# base.net
KiCad netlist of a schematic drawn in EAGLE
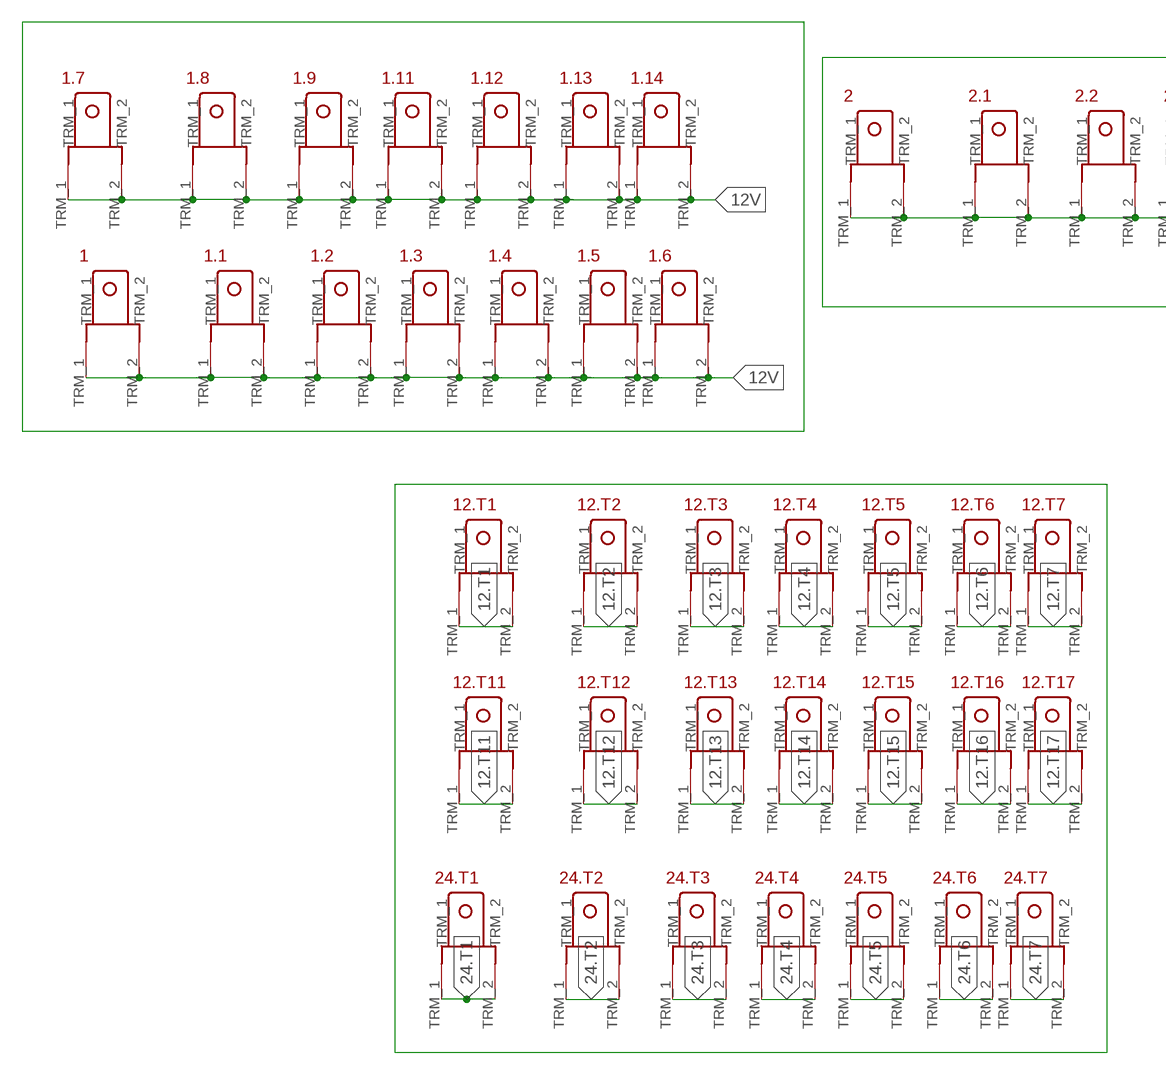
[diagram p0: schematic, sheet 1, part 1 of 2]
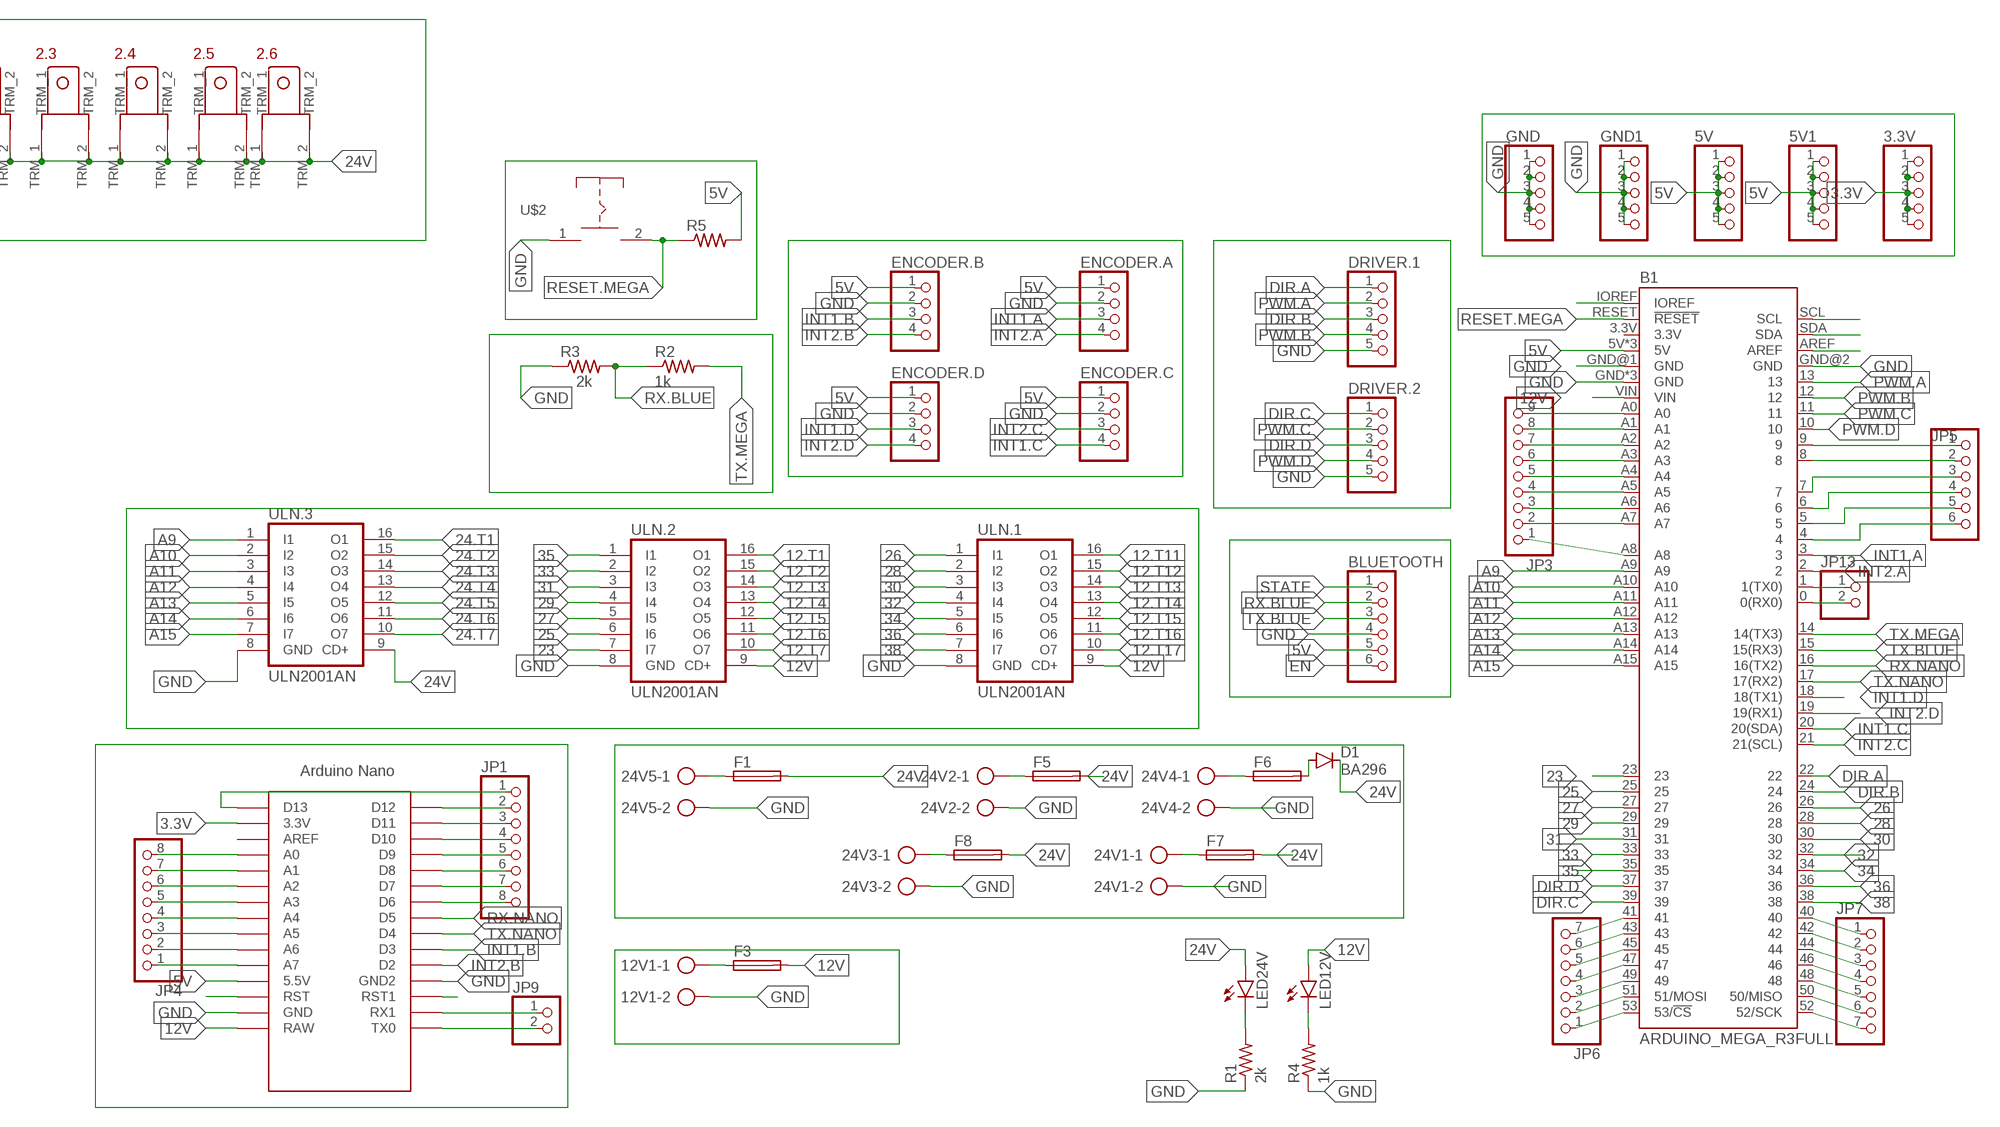
[diagram p1: schematic, sheet 1, part 2 of 2]

(export (version "E")
  (design (tool "Eeschema 10.0.6"))
  (components
    (comp (ref "1")
      (value "TERMINAL_EDITED")
      (footprint "eagle-import:TERMINAL_EDITED")
      (libsource (lib "eagle-import") (part "TERMINAL_EDITED"))
    )
    (comp (ref "1.1")
      (value "TERMINAL_EDITED")
      (footprint "eagle-import:TERMINAL_EDITED")
      (libsource (lib "eagle-import") (part "TERMINAL_EDITED"))
    )
    (comp (ref "1.2")
      (value "TERMINAL_EDITED")
      (footprint "eagle-import:TERMINAL_EDITED")
      (libsource (lib "eagle-import") (part "TERMINAL_EDITED"))
    )
    (comp (ref "1.3")
      (value "TERMINAL_EDITED")
      (footprint "eagle-import:TERMINAL_EDITED")
      (libsource (lib "eagle-import") (part "TERMINAL_EDITED"))
    )
    (comp (ref "1.4")
      (value "TERMINAL_EDITED")
      (footprint "eagle-import:TERMINAL_EDITED")
      (libsource (lib "eagle-import") (part "TERMINAL_EDITED"))
    )
    (comp (ref "1.5")
      (value "TERMINAL_EDITED")
      (footprint "eagle-import:TERMINAL_EDITED")
      (libsource (lib "eagle-import") (part "TERMINAL_EDITED"))
    )
    (comp (ref "1.6")
      (value "TERMINAL_EDITED")
      (footprint "eagle-import:TERMINAL_EDITED")
      (libsource (lib "eagle-import") (part "TERMINAL_EDITED"))
    )
    (comp (ref "1.7")
      (value "TERMINAL_EDITED")
      (footprint "eagle-import:TERMINAL_EDITED")
      (libsource (lib "eagle-import") (part "TERMINAL_EDITED"))
    )
    (comp (ref "1.8")
      (value "TERMINAL_EDITED")
      (footprint "eagle-import:TERMINAL_EDITED")
      (libsource (lib "eagle-import") (part "TERMINAL_EDITED"))
    )
    (comp (ref "1.9")
      (value "TERMINAL_EDITED")
      (footprint "eagle-import:TERMINAL_EDITED")
      (libsource (lib "eagle-import") (part "TERMINAL_EDITED"))
    )
    (comp (ref "1.11")
      (value "TERMINAL_EDITED")
      (footprint "eagle-import:TERMINAL_EDITED")
      (libsource (lib "eagle-import") (part "TERMINAL_EDITED"))
    )
    (comp (ref "1.12")
      (value "TERMINAL_EDITED")
      (footprint "eagle-import:TERMINAL_EDITED")
      (libsource (lib "eagle-import") (part "TERMINAL_EDITED"))
    )
    (comp (ref "1.13")
      (value "TERMINAL_EDITED")
      (footprint "eagle-import:TERMINAL_EDITED")
      (libsource (lib "eagle-import") (part "TERMINAL_EDITED"))
    )
    (comp (ref "1.14")
      (value "TERMINAL_EDITED")
      (footprint "eagle-import:TERMINAL_EDITED")
      (libsource (lib "eagle-import") (part "TERMINAL_EDITED"))
    )
    (comp (ref "2")
      (value "TERMINAL_EDITED")
      (footprint "eagle-import:TERMINAL_EDITED")
      (libsource (lib "eagle-import") (part "TERMINAL_EDITED"))
    )
    (comp (ref "2.1")
      (value "TERMINAL_EDITED")
      (footprint "eagle-import:TERMINAL_EDITED")
      (libsource (lib "eagle-import") (part "TERMINAL_EDITED"))
    )
    (comp (ref "2.2")
      (value "TERMINAL_EDITED")
      (footprint "eagle-import:TERMINAL_EDITED")
      (libsource (lib "eagle-import") (part "TERMINAL_EDITED"))
    )
    (comp (ref "2.3")
      (value "TERMINAL_EDITED")
      (footprint "eagle-import:TERMINAL_EDITED")
      (libsource (lib "eagle-import") (part "TERMINAL_EDITED"))
    )
    (comp (ref "2.4")
      (value "TERMINAL_EDITED")
      (footprint "eagle-import:TERMINAL_EDITED")
      (libsource (lib "eagle-import") (part "TERMINAL_EDITED"))
    )
    (comp (ref "2.5")
      (value "TERMINAL_EDITED")
      (footprint "eagle-import:TERMINAL_EDITED")
      (libsource (lib "eagle-import") (part "TERMINAL_EDITED"))
    )
    (comp (ref "2.6")
      (value "TERMINAL_EDITED")
      (footprint "eagle-import:TERMINAL_EDITED")
      (libsource (lib "eagle-import") (part "TERMINAL_EDITED"))
    )
    (comp (ref "3.3V")
      (value "PINHD-1X5")
      (footprint "eagle-import:1X05")
      (libsource (lib "eagle-import") (part "PINHD-1X5"))
    )
    (comp (ref "5V")
      (value "PINHD-1X5")
      (footprint "eagle-import:1X05")
      (libsource (lib "eagle-import") (part "PINHD-1X5"))
    )
    (comp (ref "5V1")
      (value "PINHD-1X5")
      (footprint "eagle-import:1X05")
      (libsource (lib "eagle-import") (part "PINHD-1X5"))
    )
    (comp (ref "12.T1")
      (value "TERMINAL_EDITED")
      (footprint "eagle-import:TERMINAL_EDITED")
      (libsource (lib "eagle-import") (part "TERMINAL_EDITED"))
    )
    (comp (ref "12.T2")
      (value "TERMINAL_EDITED")
      (footprint "eagle-import:TERMINAL_EDITED")
      (libsource (lib "eagle-import") (part "TERMINAL_EDITED"))
    )
    (comp (ref "12.T3")
      (value "TERMINAL_EDITED")
      (footprint "eagle-import:TERMINAL_EDITED")
      (libsource (lib "eagle-import") (part "TERMINAL_EDITED"))
    )
    (comp (ref "12.T4")
      (value "TERMINAL_EDITED")
      (footprint "eagle-import:TERMINAL_EDITED")
      (libsource (lib "eagle-import") (part "TERMINAL_EDITED"))
    )
    (comp (ref "12.T5")
      (value "TERMINAL_EDITED")
      (footprint "eagle-import:TERMINAL_EDITED")
      (libsource (lib "eagle-import") (part "TERMINAL_EDITED"))
    )
    (comp (ref "12.T6")
      (value "TERMINAL_EDITED")
      (footprint "eagle-import:TERMINAL_EDITED")
      (libsource (lib "eagle-import") (part "TERMINAL_EDITED"))
    )
    (comp (ref "12.T7")
      (value "TERMINAL_EDITED")
      (footprint "eagle-import:TERMINAL_EDITED")
      (libsource (lib "eagle-import") (part "TERMINAL_EDITED"))
    )
    (comp (ref "12.T11")
      (value "TERMINAL_EDITED")
      (footprint "eagle-import:TERMINAL_EDITED")
      (libsource (lib "eagle-import") (part "TERMINAL_EDITED"))
    )
    (comp (ref "12.T12")
      (value "TERMINAL_EDITED")
      (footprint "eagle-import:TERMINAL_EDITED")
      (libsource (lib "eagle-import") (part "TERMINAL_EDITED"))
    )
    (comp (ref "12.T13")
      (value "TERMINAL_EDITED")
      (footprint "eagle-import:TERMINAL_EDITED")
      (libsource (lib "eagle-import") (part "TERMINAL_EDITED"))
    )
    (comp (ref "12.T14")
      (value "TERMINAL_EDITED")
      (footprint "eagle-import:TERMINAL_EDITED")
      (libsource (lib "eagle-import") (part "TERMINAL_EDITED"))
    )
    (comp (ref "12.T15")
      (value "TERMINAL_EDITED")
      (footprint "eagle-import:TERMINAL_EDITED")
      (libsource (lib "eagle-import") (part "TERMINAL_EDITED"))
    )
    (comp (ref "12.T16")
      (value "TERMINAL_EDITED")
      (footprint "eagle-import:TERMINAL_EDITED")
      (libsource (lib "eagle-import") (part "TERMINAL_EDITED"))
    )
    (comp (ref "12.T17")
      (value "TERMINAL_EDITED")
      (footprint "eagle-import:TERMINAL_EDITED")
      (libsource (lib "eagle-import") (part "TERMINAL_EDITED"))
    )
    (comp (ref "12V1")
      (value "AK300/2")
      (footprint "eagle-import:AK300_2")
      (libsource (lib "eagle-import") (part "AK300/2"))
    )
    (comp (ref "24.T1")
      (value "TERMINAL_EDITED")
      (footprint "eagle-import:TERMINAL_EDITED")
      (libsource (lib "eagle-import") (part "TERMINAL_EDITED"))
    )
    (comp (ref "24.T2")
      (value "TERMINAL_EDITED")
      (footprint "eagle-import:TERMINAL_EDITED")
      (libsource (lib "eagle-import") (part "TERMINAL_EDITED"))
    )
    (comp (ref "24.T3")
      (value "TERMINAL_EDITED")
      (footprint "eagle-import:TERMINAL_EDITED")
      (libsource (lib "eagle-import") (part "TERMINAL_EDITED"))
    )
    (comp (ref "24.T4")
      (value "TERMINAL_EDITED")
      (footprint "eagle-import:TERMINAL_EDITED")
      (libsource (lib "eagle-import") (part "TERMINAL_EDITED"))
    )
    (comp (ref "24.T5")
      (value "TERMINAL_EDITED")
      (footprint "eagle-import:TERMINAL_EDITED")
      (libsource (lib "eagle-import") (part "TERMINAL_EDITED"))
    )
    (comp (ref "24.T6")
      (value "TERMINAL_EDITED")
      (footprint "eagle-import:TERMINAL_EDITED")
      (libsource (lib "eagle-import") (part "TERMINAL_EDITED"))
    )
    (comp (ref "24.T7")
      (value "TERMINAL_EDITED")
      (footprint "eagle-import:TERMINAL_EDITED")
      (libsource (lib "eagle-import") (part "TERMINAL_EDITED"))
    )
    (comp (ref "24V1")
      (value "AK300/2")
      (footprint "eagle-import:AK300_2")
      (libsource (lib "eagle-import") (part "AK300/2"))
    )
    (comp (ref "24V2")
      (value "AK300/2")
      (footprint "eagle-import:AK300_2")
      (libsource (lib "eagle-import") (part "AK300/2"))
    )
    (comp (ref "24V3")
      (value "AK300/2")
      (footprint "eagle-import:AK300_2")
      (libsource (lib "eagle-import") (part "AK300/2"))
    )
    (comp (ref "24V4")
      (value "AK300/2")
      (footprint "eagle-import:AK300_2")
      (libsource (lib "eagle-import") (part "AK300/2"))
    )
    (comp (ref "24V5")
      (value "AK300/2")
      (footprint "eagle-import:AK300_2")
      (libsource (lib "eagle-import") (part "AK300/2"))
    )
    (comp (ref "B1")
      (value "ARDUINO_MEGA_R3FULL")
      (footprint "eagle-import:ARDUINO_MEGA_NO_SILK")
      (libsource (lib "eagle-import") (part "ARDUINO_MEGA_R3FULL"))
    )
    (comp (ref "BLUETOOTH")
      (value "PINHD-1X6")
      (footprint "eagle-import:1X06")
      (libsource (lib "eagle-import") (part "PINHD-1X6"))
    )
    (comp (ref "D1")
      (value "BA296")
      (footprint "eagle-import:P2-15")
      (libsource (lib "eagle-import") (part "BA296"))
    )
    (comp (ref "DRIVER.1")
      (value "PINHD-1X5")
      (footprint "eagle-import:1X05")
      (libsource (lib "eagle-import") (part "PINHD-1X5"))
    )
    (comp (ref "DRIVER.2")
      (value "PINHD-1X5")
      (footprint "eagle-import:1X05")
      (libsource (lib "eagle-import") (part "PINHD-1X5"))
    )
    (comp (ref "ENCODER.A")
      (value "PINHD-1X4")
      (footprint "eagle-import:1X04")
      (libsource (lib "eagle-import") (part "PINHD-1X4"))
    )
    (comp (ref "ENCODER.B")
      (value "PINHD-1X4")
      (footprint "eagle-import:1X04")
      (libsource (lib "eagle-import") (part "PINHD-1X4"))
    )
    (comp (ref "ENCODER.C")
      (value "PINHD-1X4")
      (footprint "eagle-import:1X04")
      (libsource (lib "eagle-import") (part "PINHD-1X4"))
    )
    (comp (ref "ENCODER.D")
      (value "PINHD-1X4")
      (footprint "eagle-import:1X04")
      (libsource (lib "eagle-import") (part "PINHD-1X4"))
    )
    (comp (ref "F1")
      (value "SH22,5A")
      (footprint "eagle-import:SH22,5A")
      (fields (field (name "MPN") "0031.7701.11"))
      (libsource (lib "eagle-import") (part "SH22,5A"))
    )
    (comp (ref "F3")
      (value "SH22,5A")
      (footprint "eagle-import:SH22,5A")
      (fields (field (name "MPN") "0031.7701.11"))
      (libsource (lib "eagle-import") (part "SH22,5A"))
    )
    (comp (ref "F5")
      (value "SH22,5A")
      (footprint "eagle-import:SH22,5A")
      (fields (field (name "MPN") "0031.7701.11"))
      (libsource (lib "eagle-import") (part "SH22,5A"))
    )
    (comp (ref "F6")
      (value "SH22,5A")
      (footprint "eagle-import:SH22,5A")
      (fields (field (name "MPN") "0031.7701.11"))
      (libsource (lib "eagle-import") (part "SH22,5A"))
    )
    (comp (ref "F7")
      (value "SH22,5A")
      (footprint "eagle-import:SH22,5A")
      (fields (field (name "MPN") "0031.7701.11"))
      (libsource (lib "eagle-import") (part "SH22,5A"))
    )
    (comp (ref "F8")
      (value "SH22,5A")
      (footprint "eagle-import:SH22,5A")
      (fields (field (name "MPN") "0031.7701.11"))
      (libsource (lib "eagle-import") (part "SH22,5A"))
    )
    (comp (ref "GND")
      (value "PINHD-1X5")
      (footprint "eagle-import:1X05")
      (libsource (lib "eagle-import") (part "PINHD-1X5"))
    )
    (comp (ref "GND1")
      (value "PINHD-1X5")
      (footprint "eagle-import:1X05")
      (libsource (lib "eagle-import") (part "PINHD-1X5"))
    )
    (comp (ref "JP1")
      (value "PINHD-1X8")
      (footprint "eagle-import:1X08")
      (libsource (lib "eagle-import") (part "PINHD-1X8"))
    )
    (comp (ref "JP3")
      (value "PINHD-1X9")
      (footprint "eagle-import:1X09")
      (libsource (lib "eagle-import") (part "PINHD-1X9"))
    )
    (comp (ref "JP4")
      (value "PINHD-1X8")
      (footprint "eagle-import:1X08")
      (libsource (lib "eagle-import") (part "PINHD-1X8"))
    )
    (comp (ref "JP5")
      (value "PINHD-1X6")
      (footprint "eagle-import:1X06")
      (libsource (lib "eagle-import") (part "PINHD-1X6"))
    )
    (comp (ref "JP6")
      (value "PINHD-1X7")
      (footprint "eagle-import:1X07")
      (libsource (lib "eagle-import") (part "PINHD-1X7"))
    )
    (comp (ref "JP7")
      (value "PINHD-1X7")
      (footprint "eagle-import:1X07")
      (libsource (lib "eagle-import") (part "PINHD-1X7"))
    )
    (comp (ref "JP9")
      (value "PINHD-1X2")
      (footprint "eagle-import:1X02")
      (libsource (lib "eagle-import") (part "PINHD-1X2"))
    )
    (comp (ref "JP13")
      (value "PINHD-1X2")
      (footprint "eagle-import:1X02")
      (libsource (lib "eagle-import") (part "PINHD-1X2"))
    )
    (comp (ref "LED12V")
      (value "LED5MM")
      (footprint "eagle-import:LED5MM")
      (libsource (lib "eagle-import") (part "LED5MM"))
    )
    (comp (ref "LED24V")
      (value "LED5MM")
      (footprint "eagle-import:LED5MM")
      (libsource (lib "eagle-import") (part "LED5MM"))
    )
    (comp (ref "R1")
      (value "2k")
      (footprint "eagle-import:0207_10")
      (libsource (lib "eagle-import") (part "R-US_0207/10"))
    )
    (comp (ref "R2")
      (value "1k")
      (footprint "eagle-import:0204_7")
      (libsource (lib "eagle-import") (part "R-US_0204/7"))
    )
    (comp (ref "R3")
      (value "2k")
      (footprint "eagle-import:0207_10")
      (libsource (lib "eagle-import") (part "R-US_0207/10"))
    )
    (comp (ref "R4")
      (value "1k")
      (footprint "eagle-import:0207_10")
      (libsource (lib "eagle-import") (part "R-US_0207/10"))
    )
    (comp (ref "R5")
      (value "R-US_0207/12")
      (footprint "eagle-import:0207_12")
      (libsource (lib "eagle-import") (part "R-US_0207/12"))
    )
    (comp (ref "U$1")
      (value "NANO")
      (footprint "eagle-import:NANO")
      (libsource (lib "eagle-import") (part "NANO"))
    )
    (comp (ref "U$2")
      (value "PUSHBOTTON")
      (footprint "eagle-import:PUSHBOTTON")
      (libsource (lib "eagle-import") (part "PUSHBOTTON"))
    )
    (comp (ref "ULN.1")
      (value "ULN2001AN")
      (footprint "eagle-import:DIL16")
      (libsource (lib "eagle-import") (part "ULN2001AN"))
    )
    (comp (ref "ULN.2")
      (value "ULN2001AN")
      (footprint "eagle-import:DIL16")
      (libsource (lib "eagle-import") (part "ULN2001AN"))
    )
    (comp (ref "ULN.3")
      (value "ULN2001AN")
      (footprint "eagle-import:DIL16")
      (libsource (lib "eagle-import") (part "ULN2001AN"))
    )
  )
  (nets
    (net (code "1") (name "3.3V") (class "Default")
      (node (ref "3.3V") (pin "1") (pinfunction "1_1") (pintype "passive"))
      (node (ref "3.3V") (pin "2") (pinfunction "2_2") (pintype "passive"))
      (node (ref "3.3V") (pin "3") (pinfunction "3_3") (pintype "passive"))
      (node (ref "3.3V") (pin "4") (pinfunction "4_4") (pintype "passive"))
      (node (ref "3.3V") (pin "5") (pinfunction "5_5") (pintype "passive"))
      (node (ref "U$1") (pin "3.3V") (pinfunction "3.3V_3.3V") (pintype "bidirectional"))
    )
    (net (code "2") (name "5V") (class "Default")
      (node (ref "5V") (pin "1") (pinfunction "1_1") (pintype "passive"))
      (node (ref "5V") (pin "2") (pinfunction "2_2") (pintype "passive"))
      (node (ref "5V") (pin "3") (pinfunction "3_3") (pintype "passive"))
      (node (ref "5V") (pin "4") (pinfunction "4_4") (pintype "passive"))
      (node (ref "5V") (pin "5") (pinfunction "5_5") (pintype "passive"))
      (node (ref "5V1") (pin "1") (pinfunction "1_1") (pintype "passive"))
      (node (ref "5V1") (pin "2") (pinfunction "2_2") (pintype "passive"))
      (node (ref "5V1") (pin "3") (pinfunction "3_3") (pintype "passive"))
      (node (ref "5V1") (pin "4") (pinfunction "4_4") (pintype "passive"))
      (node (ref "5V1") (pin "5") (pinfunction "5_5") (pintype "passive"))
      (node (ref "B1") (pin "5V") (pinfunction "5V_5V") (pintype "bidirectional"))
      (node (ref "B1") (pin "5V@1") (pinfunction "5V_5V@1") (pintype "bidirectional"))
      (node (ref "B1") (pin "5V@2") (pinfunction "5V_5V@2") (pintype "bidirectional"))
      (node (ref "BLUETOOTH") (pin "5") (pinfunction "5_5") (pintype "passive"))
      (node (ref "ENCODER.A") (pin "1") (pinfunction "1_1") (pintype "passive"))
      (node (ref "ENCODER.B") (pin "1") (pinfunction "1_1") (pintype "passive"))
      (node (ref "ENCODER.C") (pin "1") (pinfunction "1_1") (pintype "passive"))
      (node (ref "ENCODER.D") (pin "1") (pinfunction "1_1") (pintype "passive"))
      (node (ref "R5") (pin "2") (pinfunction "2_2") (pintype "passive"))
      (node (ref "U$1") (pin "5V") (pinfunction "5.5V_5V") (pintype "bidirectional"))
    )
    (net (code "3") (name "12.T1") (class "Default")
      (node (ref "12.T1") (pin "TRM_1") (pinfunction "TRM_1_TRM_1") (pintype "bidirectional"))
      (node (ref "12.T1") (pin "TRM_2") (pinfunction "TRM_2_TRM_2") (pintype "bidirectional"))
      (node (ref "ULN.2") (pin "16") (pinfunction "O1_16") (pintype "open_collector"))
    )
    (net (code "4") (name "12.T2") (class "Default")
      (node (ref "12.T2") (pin "TRM_1") (pinfunction "TRM_1_TRM_1") (pintype "bidirectional"))
      (node (ref "12.T2") (pin "TRM_2") (pinfunction "TRM_2_TRM_2") (pintype "bidirectional"))
      (node (ref "ULN.2") (pin "15") (pinfunction "O2_15") (pintype "open_collector"))
    )
    (net (code "5") (name "12.T3") (class "Default")
      (node (ref "12.T3") (pin "TRM_1") (pinfunction "TRM_1_TRM_1") (pintype "bidirectional"))
      (node (ref "12.T3") (pin "TRM_2") (pinfunction "TRM_2_TRM_2") (pintype "bidirectional"))
      (node (ref "ULN.2") (pin "14") (pinfunction "O3_14") (pintype "open_collector"))
    )
    (net (code "6") (name "12.T4") (class "Default")
      (node (ref "12.T4") (pin "TRM_1") (pinfunction "TRM_1_TRM_1") (pintype "bidirectional"))
      (node (ref "12.T4") (pin "TRM_2") (pinfunction "TRM_2_TRM_2") (pintype "bidirectional"))
      (node (ref "ULN.2") (pin "13") (pinfunction "O4_13") (pintype "open_collector"))
    )
    (net (code "7") (name "12.T5") (class "Default")
      (node (ref "12.T5") (pin "TRM_1") (pinfunction "TRM_1_TRM_1") (pintype "bidirectional"))
      (node (ref "12.T5") (pin "TRM_2") (pinfunction "TRM_2_TRM_2") (pintype "bidirectional"))
      (node (ref "ULN.2") (pin "12") (pinfunction "O5_12") (pintype "open_collector"))
    )
    (net (code "8") (name "12.T6") (class "Default")
      (node (ref "12.T6") (pin "TRM_1") (pinfunction "TRM_1_TRM_1") (pintype "bidirectional"))
      (node (ref "12.T6") (pin "TRM_2") (pinfunction "TRM_2_TRM_2") (pintype "bidirectional"))
      (node (ref "ULN.2") (pin "11") (pinfunction "O6_11") (pintype "open_collector"))
    )
    (net (code "9") (name "12.T7") (class "Default")
      (node (ref "12.T7") (pin "TRM_1") (pinfunction "TRM_1_TRM_1") (pintype "bidirectional"))
      (node (ref "12.T7") (pin "TRM_2") (pinfunction "TRM_2_TRM_2") (pintype "bidirectional"))
      (node (ref "ULN.2") (pin "10") (pinfunction "O7_10") (pintype "open_collector"))
    )
    (net (code "10") (name "12.T11") (class "Default")
      (node (ref "12.T11") (pin "TRM_1") (pinfunction "TRM_1_TRM_1") (pintype "bidirectional"))
      (node (ref "12.T11") (pin "TRM_2") (pinfunction "TRM_2_TRM_2") (pintype "bidirectional"))
      (node (ref "ULN.1") (pin "16") (pinfunction "O1_16") (pintype "open_collector"))
    )
    (net (code "11") (name "12.T12") (class "Default")
      (node (ref "12.T12") (pin "TRM_1") (pinfunction "TRM_1_TRM_1") (pintype "bidirectional"))
      (node (ref "12.T12") (pin "TRM_2") (pinfunction "TRM_2_TRM_2") (pintype "bidirectional"))
      (node (ref "ULN.1") (pin "15") (pinfunction "O2_15") (pintype "open_collector"))
    )
    (net (code "12") (name "12.T13") (class "Default")
      (node (ref "12.T13") (pin "TRM_1") (pinfunction "TRM_1_TRM_1") (pintype "bidirectional"))
      (node (ref "12.T13") (pin "TRM_2") (pinfunction "TRM_2_TRM_2") (pintype "bidirectional"))
      (node (ref "ULN.1") (pin "14") (pinfunction "O3_14") (pintype "open_collector"))
    )
    (net (code "13") (name "12.T14") (class "Default")
      (node (ref "12.T14") (pin "TRM_1") (pinfunction "TRM_1_TRM_1") (pintype "bidirectional"))
      (node (ref "12.T14") (pin "TRM_2") (pinfunction "TRM_2_TRM_2") (pintype "bidirectional"))
      (node (ref "ULN.1") (pin "13") (pinfunction "O4_13") (pintype "open_collector"))
    )
    (net (code "14") (name "12.T15") (class "Default")
      (node (ref "12.T15") (pin "TRM_1") (pinfunction "TRM_1_TRM_1") (pintype "bidirectional"))
      (node (ref "12.T15") (pin "TRM_2") (pinfunction "TRM_2_TRM_2") (pintype "bidirectional"))
      (node (ref "ULN.1") (pin "12") (pinfunction "O5_12") (pintype "open_collector"))
    )
    (net (code "15") (name "12.T16") (class "Default")
      (node (ref "12.T16") (pin "TRM_1") (pinfunction "TRM_1_TRM_1") (pintype "bidirectional"))
      (node (ref "12.T16") (pin "TRM_2") (pinfunction "TRM_2_TRM_2") (pintype "bidirectional"))
      (node (ref "ULN.1") (pin "11") (pinfunction "O6_11") (pintype "open_collector"))
    )
    (net (code "16") (name "12.T17") (class "Default")
      (node (ref "12.T17") (pin "TRM_1") (pinfunction "TRM_1_TRM_1") (pintype "bidirectional"))
      (node (ref "12.T17") (pin "TRM_2") (pinfunction "TRM_2_TRM_2") (pintype "bidirectional"))
      (node (ref "ULN.1") (pin "10") (pinfunction "O7_10") (pintype "open_collector"))
    )
    (net (code "17") (name "12V") (class "Default")
      (node (ref "1") (pin "TRM_1") (pinfunction "TRM_1_TRM_1") (pintype "bidirectional"))
      (node (ref "1") (pin "TRM_2") (pinfunction "TRM_2_TRM_2") (pintype "bidirectional"))
      (node (ref "1.1") (pin "TRM_1") (pinfunction "TRM_1_TRM_1") (pintype "bidirectional"))
      (node (ref "1.1") (pin "TRM_2") (pinfunction "TRM_2_TRM_2") (pintype "bidirectional"))
      (node (ref "1.11") (pin "TRM_1") (pinfunction "TRM_1_TRM_1") (pintype "bidirectional"))
      (node (ref "1.11") (pin "TRM_2") (pinfunction "TRM_2_TRM_2") (pintype "bidirectional"))
      (node (ref "1.12") (pin "TRM_1") (pinfunction "TRM_1_TRM_1") (pintype "bidirectional"))
      (node (ref "1.12") (pin "TRM_2") (pinfunction "TRM_2_TRM_2") (pintype "bidirectional"))
      (node (ref "1.13") (pin "TRM_1") (pinfunction "TRM_1_TRM_1") (pintype "bidirectional"))
      (node (ref "1.13") (pin "TRM_2") (pinfunction "TRM_2_TRM_2") (pintype "bidirectional"))
      (node (ref "1.14") (pin "TRM_1") (pinfunction "TRM_1_TRM_1") (pintype "bidirectional"))
      (node (ref "1.14") (pin "TRM_2") (pinfunction "TRM_2_TRM_2") (pintype "bidirectional"))
      (node (ref "1.2") (pin "TRM_1") (pinfunction "TRM_1_TRM_1") (pintype "bidirectional"))
      (node (ref "1.2") (pin "TRM_2") (pinfunction "TRM_2_TRM_2") (pintype "bidirectional"))
      (node (ref "1.3") (pin "TRM_1") (pinfunction "TRM_1_TRM_1") (pintype "bidirectional"))
      (node (ref "1.3") (pin "TRM_2") (pinfunction "TRM_2_TRM_2") (pintype "bidirectional"))
      (node (ref "1.4") (pin "TRM_1") (pinfunction "TRM_1_TRM_1") (pintype "bidirectional"))
      (node (ref "1.4") (pin "TRM_2") (pinfunction "TRM_2_TRM_2") (pintype "bidirectional"))
      (node (ref "1.5") (pin "TRM_1") (pinfunction "TRM_1_TRM_1") (pintype "bidirectional"))
      (node (ref "1.5") (pin "TRM_2") (pinfunction "TRM_2_TRM_2") (pintype "bidirectional"))
      (node (ref "1.6") (pin "TRM_1") (pinfunction "TRM_1_TRM_1") (pintype "bidirectional"))
      (node (ref "1.6") (pin "TRM_2") (pinfunction "TRM_2_TRM_2") (pintype "bidirectional"))
      (node (ref "1.7") (pin "TRM_1") (pinfunction "TRM_1_TRM_1") (pintype "bidirectional"))
      (node (ref "1.7") (pin "TRM_2") (pinfunction "TRM_2_TRM_2") (pintype "bidirectional"))
      (node (ref "1.8") (pin "TRM_1") (pinfunction "TRM_1_TRM_1") (pintype "bidirectional"))
      (node (ref "1.8") (pin "TRM_2") (pinfunction "TRM_2_TRM_2") (pintype "bidirectional"))
      (node (ref "1.9") (pin "TRM_1") (pinfunction "TRM_1_TRM_1") (pintype "bidirectional"))
      (node (ref "1.9") (pin "TRM_2") (pinfunction "TRM_2_TRM_2") (pintype "bidirectional"))
      (node (ref "B1") (pin "VIN") (pinfunction "VIN_VIN") (pintype "bidirectional"))
      (node (ref "F3") (pin "2") (pinfunction "2_2") (pintype "passive"))
      (node (ref "LED12V") (pin "A") (pinfunction "A_A") (pintype "passive"))
      (node (ref "U$1") (pin "RAW") (pinfunction "RAW_RAW") (pintype "bidirectional"))
      (node (ref "ULN.1") (pin "9") (pinfunction "CD+_9") (pintype "passive"))
      (node (ref "ULN.2") (pin "9") (pinfunction "CD+_9") (pintype "passive"))
    )
    (net (code "18") (name "23") (class "Default")
      (node (ref "B1") (pin "23") (pinfunction "23_23") (pintype "bidirectional"))
      (node (ref "ULN.2") (pin "7") (pinfunction "I7_7") (pintype "input"))
    )
    (net (code "19") (name "24.T1") (class "Default")
      (node (ref "24.T1") (pin "TRM_1") (pinfunction "TRM_1_TRM_1") (pintype "bidirectional"))
      (node (ref "24.T1") (pin "TRM_2") (pinfunction "TRM_2_TRM_2") (pintype "bidirectional"))
      (node (ref "ULN.3") (pin "16") (pinfunction "O1_16") (pintype "open_collector"))
    )
    (net (code "20") (name "24.T2") (class "Default")
      (node (ref "24.T2") (pin "TRM_1") (pinfunction "TRM_1_TRM_1") (pintype "bidirectional"))
      (node (ref "24.T2") (pin "TRM_2") (pinfunction "TRM_2_TRM_2") (pintype "bidirectional"))
      (node (ref "ULN.3") (pin "15") (pinfunction "O2_15") (pintype "open_collector"))
    )
    (net (code "21") (name "24.T3") (class "Default")
      (node (ref "24.T3") (pin "TRM_1") (pinfunction "TRM_1_TRM_1") (pintype "bidirectional"))
      (node (ref "24.T3") (pin "TRM_2") (pinfunction "TRM_2_TRM_2") (pintype "bidirectional"))
      (node (ref "ULN.3") (pin "14") (pinfunction "O3_14") (pintype "open_collector"))
    )
    (net (code "22") (name "24.T4") (class "Default")
      (node (ref "24.T4") (pin "TRM_1") (pinfunction "TRM_1_TRM_1") (pintype "bidirectional"))
      (node (ref "24.T4") (pin "TRM_2") (pinfunction "TRM_2_TRM_2") (pintype "bidirectional"))
      (node (ref "ULN.3") (pin "13") (pinfunction "O4_13") (pintype "open_collector"))
    )
    (net (code "23") (name "24.T5") (class "Default")
      (node (ref "24.T5") (pin "TRM_1") (pinfunction "TRM_1_TRM_1") (pintype "bidirectional"))
      (node (ref "24.T5") (pin "TRM_2") (pinfunction "TRM_2_TRM_2") (pintype "bidirectional"))
      (node (ref "ULN.3") (pin "12") (pinfunction "O5_12") (pintype "open_collector"))
    )
    (net (code "24") (name "24.T6") (class "Default")
      (node (ref "24.T6") (pin "TRM_1") (pinfunction "TRM_1_TRM_1") (pintype "bidirectional"))
      (node (ref "24.T6") (pin "TRM_2") (pinfunction "TRM_2_TRM_2") (pintype "bidirectional"))
      (node (ref "ULN.3") (pin "11") (pinfunction "O6_11") (pintype "open_collector"))
    )
    (net (code "25") (name "24.T7") (class "Default")
      (node (ref "24.T7") (pin "TRM_1") (pinfunction "TRM_1_TRM_1") (pintype "bidirectional"))
      (node (ref "24.T7") (pin "TRM_2") (pinfunction "TRM_2_TRM_2") (pintype "bidirectional"))
      (node (ref "ULN.3") (pin "10") (pinfunction "O7_10") (pintype "open_collector"))
    )
    (net (code "26") (name "24V") (class "Default")
      (node (ref "2") (pin "TRM_1") (pinfunction "TRM_1_TRM_1") (pintype "bidirectional"))
      (node (ref "2") (pin "TRM_2") (pinfunction "TRM_2_TRM_2") (pintype "bidirectional"))
      (node (ref "2.1") (pin "TRM_1") (pinfunction "TRM_1_TRM_1") (pintype "bidirectional"))
      (node (ref "2.1") (pin "TRM_2") (pinfunction "TRM_2_TRM_2") (pintype "bidirectional"))
      (node (ref "2.2") (pin "TRM_1") (pinfunction "TRM_1_TRM_1") (pintype "bidirectional"))
      (node (ref "2.2") (pin "TRM_2") (pinfunction "TRM_2_TRM_2") (pintype "bidirectional"))
      (node (ref "2.3") (pin "TRM_1") (pinfunction "TRM_1_TRM_1") (pintype "bidirectional"))
      (node (ref "2.3") (pin "TRM_2") (pinfunction "TRM_2_TRM_2") (pintype "bidirectional"))
      (node (ref "2.4") (pin "TRM_1") (pinfunction "TRM_1_TRM_1") (pintype "bidirectional"))
      (node (ref "2.4") (pin "TRM_2") (pinfunction "TRM_2_TRM_2") (pintype "bidirectional"))
      (node (ref "2.5") (pin "TRM_1") (pinfunction "TRM_1_TRM_1") (pintype "bidirectional"))
      (node (ref "2.5") (pin "TRM_2") (pinfunction "TRM_2_TRM_2") (pintype "bidirectional"))
      (node (ref "2.6") (pin "TRM_1") (pinfunction "TRM_1_TRM_1") (pintype "bidirectional"))
      (node (ref "2.6") (pin "TRM_2") (pinfunction "TRM_2_TRM_2") (pintype "bidirectional"))
      (node (ref "D1") (pin "C") (pinfunction "C_C") (pintype "passive"))
      (node (ref "F1") (pin "2") (pinfunction "2_2") (pintype "passive"))
      (node (ref "F5") (pin "2") (pinfunction "2_2") (pintype "passive"))
      (node (ref "F7") (pin "2") (pinfunction "2_2") (pintype "passive"))
      (node (ref "F8") (pin "2") (pinfunction "2_2") (pintype "passive"))
      (node (ref "LED24V") (pin "A") (pinfunction "A_A") (pintype "passive"))
      (node (ref "ULN.3") (pin "9") (pinfunction "CD+_9") (pintype "passive"))
    )
    (net (code "27") (name "25") (class "Default")
      (node (ref "B1") (pin "25") (pinfunction "25_25") (pintype "bidirectional"))
      (node (ref "ULN.2") (pin "6") (pinfunction "I6_6") (pintype "input"))
    )
    (net (code "28") (name "26") (class "Default")
      (node (ref "B1") (pin "26") (pinfunction "26_26") (pintype "bidirectional"))
      (node (ref "ULN.1") (pin "1") (pinfunction "I1_1") (pintype "input"))
    )
    (net (code "29") (name "27") (class "Default")
      (node (ref "B1") (pin "27") (pinfunction "27_27") (pintype "bidirectional"))
      (node (ref "ULN.2") (pin "5") (pinfunction "I5_5") (pintype "input"))
    )
    (net (code "30") (name "28") (class "Default")
      (node (ref "B1") (pin "28") (pinfunction "28_28") (pintype "bidirectional"))
      (node (ref "ULN.1") (pin "2") (pinfunction "I2_2") (pintype "input"))
    )
    (net (code "31") (name "29") (class "Default")
      (node (ref "B1") (pin "29") (pinfunction "29_29") (pintype "bidirectional"))
      (node (ref "ULN.2") (pin "4") (pinfunction "I4_4") (pintype "input"))
    )
    (net (code "32") (name "30") (class "Default")
      (node (ref "B1") (pin "30") (pinfunction "30_30") (pintype "bidirectional"))
      (node (ref "ULN.1") (pin "3") (pinfunction "I3_3") (pintype "input"))
    )
    (net (code "33") (name "31") (class "Default")
      (node (ref "B1") (pin "31") (pinfunction "31_31") (pintype "bidirectional"))
      (node (ref "ULN.2") (pin "3") (pinfunction "I3_3") (pintype "input"))
    )
    (net (code "34") (name "32") (class "Default")
      (node (ref "B1") (pin "32") (pinfunction "32_32") (pintype "bidirectional"))
      (node (ref "ULN.1") (pin "4") (pinfunction "I4_4") (pintype "input"))
    )
    (net (code "35") (name "33") (class "Default")
      (node (ref "B1") (pin "33") (pinfunction "33_33") (pintype "bidirectional"))
      (node (ref "ULN.2") (pin "2") (pinfunction "I2_2") (pintype "input"))
    )
    (net (code "36") (name "34") (class "Default")
      (node (ref "B1") (pin "34") (pinfunction "34_34") (pintype "bidirectional"))
      (node (ref "ULN.1") (pin "5") (pinfunction "I5_5") (pintype "input"))
    )
    (net (code "37") (name "35") (class "Default")
      (node (ref "B1") (pin "35") (pinfunction "35_35") (pintype "bidirectional"))
      (node (ref "ULN.2") (pin "1") (pinfunction "I1_1") (pintype "input"))
    )
    (net (code "38") (name "36") (class "Default")
      (node (ref "B1") (pin "36") (pinfunction "36_36") (pintype "bidirectional"))
      (node (ref "ULN.1") (pin "6") (pinfunction "I6_6") (pintype "input"))
    )
    (net (code "39") (name "38") (class "Default")
      (node (ref "B1") (pin "38") (pinfunction "38_38") (pintype "bidirectional"))
      (node (ref "ULN.1") (pin "7") (pinfunction "I7_7") (pintype "input"))
    )
    (net (code "40") (name "A9") (class "Default")
      (node (ref "B1") (pin "A9") (pinfunction "A9_A9") (pintype "bidirectional"))
      (node (ref "ULN.3") (pin "1") (pinfunction "I1_1") (pintype "input"))
    )
    (net (code "41") (name "A10") (class "Default")
      (node (ref "B1") (pin "A10") (pinfunction "A10_A10") (pintype "bidirectional"))
      (node (ref "ULN.3") (pin "2") (pinfunction "I2_2") (pintype "input"))
    )
    (net (code "42") (name "A11") (class "Default")
      (node (ref "B1") (pin "A11") (pinfunction "A11_A11") (pintype "bidirectional"))
      (node (ref "ULN.3") (pin "3") (pinfunction "I3_3") (pintype "input"))
    )
    (net (code "43") (name "A12") (class "Default")
      (node (ref "B1") (pin "A12") (pinfunction "A12_A12") (pintype "bidirectional"))
      (node (ref "ULN.3") (pin "4") (pinfunction "I4_4") (pintype "input"))
    )
    (net (code "44") (name "A13") (class "Default")
      (node (ref "B1") (pin "A13") (pinfunction "A13_A13") (pintype "bidirectional"))
      (node (ref "ULN.3") (pin "5") (pinfunction "I5_5") (pintype "input"))
    )
    (net (code "45") (name "A14") (class "Default")
      (node (ref "B1") (pin "A14") (pinfunction "A14_A14") (pintype "bidirectional"))
      (node (ref "ULN.3") (pin "6") (pinfunction "I6_6") (pintype "input"))
    )
    (net (code "46") (name "A15") (class "Default")
      (node (ref "B1") (pin "A15") (pinfunction "A15_A15") (pintype "bidirectional"))
      (node (ref "ULN.3") (pin "7") (pinfunction "I7_7") (pintype "input"))
    )
    (net (code "47") (name "DIR.A") (class "Default")
      (node (ref "B1") (pin "22") (pinfunction "22_22") (pintype "bidirectional"))
      (node (ref "DRIVER.1") (pin "1") (pinfunction "1_1") (pintype "passive"))
    )
    (net (code "48") (name "DIR.B") (class "Default")
      (node (ref "B1") (pin "24") (pinfunction "24_24") (pintype "bidirectional"))
      (node (ref "DRIVER.1") (pin "3") (pinfunction "3_3") (pintype "passive"))
    )
    (net (code "49") (name "DIR.C") (class "Default")
      (node (ref "B1") (pin "39") (pinfunction "39_39") (pintype "bidirectional"))
      (node (ref "DRIVER.2") (pin "1") (pinfunction "1_1") (pintype "passive"))
    )
    (net (code "50") (name "DIR.D") (class "Default")
      (node (ref "B1") (pin "37") (pinfunction "37_37") (pintype "bidirectional"))
      (node (ref "DRIVER.2") (pin "3") (pinfunction "3_3") (pintype "passive"))
    )
    (net (code "51") (name "EN") (class "Default")
      (node (ref "BLUETOOTH") (pin "6") (pinfunction "6_6") (pintype "passive"))
    )
    (net (code "52") (name "GND") (class "Default")
      (node (ref "12V1") (pin "2") (pinfunction "KL_2") (pintype "passive"))
      (node (ref "24V1") (pin "2") (pinfunction "KL_2") (pintype "passive"))
      (node (ref "24V2") (pin "2") (pinfunction "KL_2") (pintype "passive"))
      (node (ref "24V3") (pin "2") (pinfunction "KL_2") (pintype "passive"))
      (node (ref "24V4") (pin "2") (pinfunction "KL_2") (pintype "passive"))
      (node (ref "24V5") (pin "2") (pinfunction "KL_2") (pintype "passive"))
      (node (ref "B1") (pin "GND") (pinfunction "GND_GND") (pintype "bidirectional"))
      (node (ref "B1") (pin "GND@1") (pinfunction "GND_GND@1") (pintype "bidirectional"))
      (node (ref "B1") (pin "GND@2") (pinfunction "GND_GND@2") (pintype "bidirectional"))
      (node (ref "B1") (pin "GND@3") (pinfunction "GND_GND@3") (pintype "bidirectional"))
      (node (ref "B1") (pin "GND@4") (pinfunction "GND_GND@4") (pintype "bidirectional"))
      (node (ref "BLUETOOTH") (pin "4") (pinfunction "4_4") (pintype "passive"))
      (node (ref "DRIVER.1") (pin "5") (pinfunction "5_5") (pintype "passive"))
      (node (ref "DRIVER.2") (pin "5") (pinfunction "5_5") (pintype "passive"))
      (node (ref "ENCODER.A") (pin "2") (pinfunction "2_2") (pintype "passive"))
      (node (ref "ENCODER.B") (pin "2") (pinfunction "2_2") (pintype "passive"))
      (node (ref "ENCODER.C") (pin "2") (pinfunction "2_2") (pintype "passive"))
      (node (ref "ENCODER.D") (pin "2") (pinfunction "2_2") (pintype "passive"))
      (node (ref "GND") (pin "1") (pinfunction "1_1") (pintype "passive"))
      (node (ref "GND") (pin "2") (pinfunction "2_2") (pintype "passive"))
      (node (ref "GND") (pin "3") (pinfunction "3_3") (pintype "passive"))
      (node (ref "GND") (pin "4") (pinfunction "4_4") (pintype "passive"))
      (node (ref "GND") (pin "5") (pinfunction "5_5") (pintype "passive"))
      (node (ref "GND1") (pin "1") (pinfunction "1_1") (pintype "passive"))
      (node (ref "GND1") (pin "2") (pinfunction "2_2") (pintype "passive"))
      (node (ref "GND1") (pin "3") (pinfunction "3_3") (pintype "passive"))
      (node (ref "GND1") (pin "4") (pinfunction "4_4") (pintype "passive"))
      (node (ref "GND1") (pin "5") (pinfunction "5_5") (pintype "passive"))
      (node (ref "R1") (pin "1") (pinfunction "1_1") (pintype "passive"))
      (node (ref "R3") (pin "1") (pinfunction "1_1") (pintype "passive"))
      (node (ref "R4") (pin "1") (pinfunction "1_1") (pintype "passive"))
      (node (ref "U$1") (pin "GND") (pinfunction "GND_GND") (pintype "bidirectional"))
      (node (ref "U$1") (pin "GND1") (pinfunction "GND2_GND1") (pintype "bidirectional"))
      (node (ref "U$2") (pin "1") (pinfunction "1_1") (pintype "bidirectional"))
      (node (ref "ULN.1") (pin "8") (pinfunction "GND_8") (pintype "power_in"))
      (node (ref "ULN.2") (pin "8") (pinfunction "GND_8") (pintype "power_in"))
      (node (ref "ULN.3") (pin "8") (pinfunction "GND_8") (pintype "power_in"))
    )
    (net (code "53") (name "INT1.A") (class "Default")
      (node (ref "B1") (pin "3") (pinfunction "3_3") (pintype "bidirectional"))
      (node (ref "ENCODER.A") (pin "3") (pinfunction "3_3") (pintype "passive"))
    )
    (net (code "54") (name "INT1.B") (class "Default")
      (node (ref "ENCODER.B") (pin "3") (pinfunction "3_3") (pintype "passive"))
      (node (ref "U$1") (pin "D3") (pinfunction "D3_D3") (pintype "bidirectional"))
    )
    (net (code "55") (name "INT1.C") (class "Default")
      (node (ref "B1") (pin "20") (pinfunction "20(SDA)_20") (pintype "bidirectional"))
      (node (ref "ENCODER.C") (pin "4") (pinfunction "4_4") (pintype "passive"))
    )
    (net (code "56") (name "INT1.D") (class "Default")
      (node (ref "B1") (pin "18") (pinfunction "18(TX1)_18") (pintype "bidirectional"))
      (node (ref "ENCODER.D") (pin "3") (pinfunction "3_3") (pintype "passive"))
    )
    (net (code "57") (name "INT2.A") (class "Default")
      (node (ref "B1") (pin "2") (pinfunction "2_2") (pintype "bidirectional"))
      (node (ref "ENCODER.A") (pin "4") (pinfunction "4_4") (pintype "passive"))
    )
    (net (code "58") (name "INT2.B") (class "Default")
      (node (ref "ENCODER.B") (pin "4") (pinfunction "4_4") (pintype "passive"))
      (node (ref "U$1") (pin "D2") (pinfunction "D2_D2") (pintype "bidirectional"))
    )
    (net (code "59") (name "INT2.C") (class "Default")
      (node (ref "B1") (pin "21") (pinfunction "21(SCL)_21") (pintype "bidirectional"))
      (node (ref "ENCODER.C") (pin "3") (pinfunction "3_3") (pintype "passive"))
    )
    (net (code "60") (name "INT2.D") (class "Default")
      (node (ref "B1") (pin "19") (pinfunction "19(RX1)_19") (pintype "bidirectional"))
      (node (ref "ENCODER.D") (pin "4") (pinfunction "4_4") (pintype "passive"))
    )
    (net (code "61") (name "Net-(12V1A-KL)") (class "Default")
      (node (ref "12V1") (pin "1") (pinfunction "KL_1") (pintype "passive"))
      (node (ref "F3") (pin "1") (pinfunction "1_1") (pintype "passive"))
    )
    (net (code "62") (name "Net-(24V1A-KL)") (class "Default")
      (node (ref "24V1") (pin "1") (pinfunction "KL_1") (pintype "passive"))
      (node (ref "F7") (pin "1") (pinfunction "1_1") (pintype "passive"))
    )
    (net (code "63") (name "Net-(24V2A-KL)") (class "Default")
      (node (ref "24V2") (pin "1") (pinfunction "KL_1") (pintype "passive"))
      (node (ref "F5") (pin "1") (pinfunction "1_1") (pintype "passive"))
    )
    (net (code "64") (name "Net-(24V3A-KL)") (class "Default")
      (node (ref "24V3") (pin "1") (pinfunction "KL_1") (pintype "passive"))
      (node (ref "F8") (pin "1") (pinfunction "1_1") (pintype "passive"))
    )
    (net (code "65") (name "Net-(24V4A-KL)") (class "Default")
      (node (ref "24V4") (pin "1") (pinfunction "KL_1") (pintype "passive"))
      (node (ref "F6") (pin "1") (pinfunction "1_1") (pintype "passive"))
    )
    (net (code "66") (name "Net-(24V5A-KL)") (class "Default")
      (node (ref "24V5") (pin "1") (pinfunction "KL_1") (pintype "passive"))
      (node (ref "F1") (pin "1") (pinfunction "1_1") (pintype "passive"))
    )
    (net (code "67") (name "Net-(B1-0(RX0))") (class "Default")
      (node (ref "B1") (pin "0") (pinfunction "0(RX0)_0") (pintype "bidirectional"))
      (node (ref "JP13") (pin "2") (pinfunction "2_2") (pintype "passive"))
    )
    (net (code "68") (name "Net-(B1-1(TX0))") (class "Default")
      (node (ref "B1") (pin "1") (pinfunction "1(TX0)_1") (pintype "bidirectional"))
      (node (ref "JP13") (pin "1") (pinfunction "1_1") (pintype "passive"))
    )
    (net (code "69") (name "Net-(B1-50{slash}MISO)") (class "Default")
      (node (ref "B1") (pin "50") (pinfunction "50/MISO_50") (pintype "bidirectional"))
      (node (ref "JP7") (pin "6") (pinfunction "6_6") (pintype "passive"))
    )
    (net (code "70") (name "Net-(B1-51{slash}MOSI)") (class "Default")
      (node (ref "B1") (pin "51") (pinfunction "51/MOSI_51") (pintype "bidirectional"))
      (node (ref "JP6") (pin "2") (pinfunction "2_2") (pintype "passive"))
    )
    (net (code "71") (name "Net-(B1-52{slash}SCK)") (class "Default")
      (node (ref "B1") (pin "52") (pinfunction "52/SCK_52") (pintype "bidirectional"))
      (node (ref "JP7") (pin "7") (pinfunction "7_7") (pintype "passive"))
    )
    (net (code "72") (name "Net-(B1-53{slash}~{CS})") (class "Default")
      (node (ref "B1") (pin "53") (pinfunction "53/~{CS}_53") (pintype "bidirectional"))
      (node (ref "JP6") (pin "1") (pinfunction "1_1") (pintype "passive"))
    )
    (net (code "73") (name "Net-(B1-Pad4)") (class "Default")
      (node (ref "B1") (pin "4") (pinfunction "4_4") (pintype "bidirectional"))
      (node (ref "JP5") (pin "6") (pinfunction "6_6") (pintype "passive"))
    )
    (net (code "74") (name "Net-(B1-Pad5)") (class "Default")
      (node (ref "B1") (pin "5") (pinfunction "5_5") (pintype "bidirectional"))
      (node (ref "JP5") (pin "5") (pinfunction "5_5") (pintype "passive"))
    )
    (net (code "75") (name "Net-(B1-Pad6)") (class "Default")
      (node (ref "B1") (pin "6") (pinfunction "6_6") (pintype "bidirectional"))
      (node (ref "JP5") (pin "4") (pinfunction "4_4") (pintype "passive"))
    )
    (net (code "76") (name "Net-(B1-Pad7)") (class "Default")
      (node (ref "B1") (pin "7") (pinfunction "7_7") (pintype "bidirectional"))
      (node (ref "JP5") (pin "3") (pinfunction "3_3") (pintype "passive"))
    )
    (net (code "77") (name "Net-(B1-Pad8)") (class "Default")
      (node (ref "B1") (pin "8") (pinfunction "8_8") (pintype "bidirectional"))
      (node (ref "JP5") (pin "2") (pinfunction "2_2") (pintype "passive"))
    )
    (net (code "78") (name "Net-(B1-Pad9)") (class "Default")
      (node (ref "B1") (pin "9") (pinfunction "9_9") (pintype "bidirectional"))
      (node (ref "JP5") (pin "1") (pinfunction "1_1") (pintype "passive"))
    )
    (net (code "79") (name "Net-(B1-Pad40)") (class "Default")
      (node (ref "B1") (pin "40") (pinfunction "40_40") (pintype "bidirectional"))
      (node (ref "JP7") (pin "1") (pinfunction "1_1") (pintype "passive"))
    )
    (net (code "80") (name "Net-(B1-Pad41)") (class "Default")
      (node (ref "B1") (pin "41") (pinfunction "41_41") (pintype "bidirectional"))
      (node (ref "JP6") (pin "7") (pinfunction "7_7") (pintype "passive"))
    )
    (net (code "81") (name "Net-(B1-Pad42)") (class "Default")
      (node (ref "B1") (pin "42") (pinfunction "42_42") (pintype "bidirectional"))
      (node (ref "JP7") (pin "2") (pinfunction "2_2") (pintype "passive"))
    )
    (net (code "82") (name "Net-(B1-Pad43)") (class "Default")
      (node (ref "B1") (pin "43") (pinfunction "43_43") (pintype "bidirectional"))
      (node (ref "JP6") (pin "6") (pinfunction "6_6") (pintype "passive"))
    )
    (net (code "83") (name "Net-(B1-Pad44)") (class "Default")
      (node (ref "B1") (pin "44") (pinfunction "44_44") (pintype "bidirectional"))
      (node (ref "JP7") (pin "3") (pinfunction "3_3") (pintype "passive"))
    )
    (net (code "84") (name "Net-(B1-Pad45)") (class "Default")
      (node (ref "B1") (pin "45") (pinfunction "45_45") (pintype "bidirectional"))
      (node (ref "JP6") (pin "5") (pinfunction "5_5") (pintype "passive"))
    )
    (net (code "85") (name "Net-(B1-Pad46)") (class "Default")
      (node (ref "B1") (pin "46") (pinfunction "46_46") (pintype "bidirectional"))
      (node (ref "JP7") (pin "4") (pinfunction "4_4") (pintype "passive"))
    )
    (net (code "86") (name "Net-(B1-Pad47)") (class "Default")
      (node (ref "B1") (pin "47") (pinfunction "47_47") (pintype "bidirectional"))
      (node (ref "JP6") (pin "4") (pinfunction "4_4") (pintype "passive"))
    )
    (net (code "87") (name "Net-(B1-Pad48)") (class "Default")
      (node (ref "B1") (pin "48") (pinfunction "48_48") (pintype "bidirectional"))
      (node (ref "JP7") (pin "5") (pinfunction "5_5") (pintype "passive"))
    )
    (net (code "88") (name "Net-(B1-Pad49)") (class "Default")
      (node (ref "B1") (pin "49") (pinfunction "49_49") (pintype "bidirectional"))
      (node (ref "JP6") (pin "3") (pinfunction "3_3") (pintype "passive"))
    )
    (net (code "89") (name "Net-(B1-PadA0)") (class "Default")
      (node (ref "B1") (pin "A0") (pinfunction "A0_A0") (pintype "bidirectional"))
      (node (ref "JP3") (pin "9") (pinfunction "9_9") (pintype "passive"))
    )
    (net (code "90") (name "Net-(B1-PadA1)") (class "Default")
      (node (ref "B1") (pin "A1") (pinfunction "A1_A1") (pintype "bidirectional"))
      (node (ref "JP3") (pin "8") (pinfunction "8_8") (pintype "passive"))
    )
    (net (code "91") (name "Net-(B1-PadA2)") (class "Default")
      (node (ref "B1") (pin "A2") (pinfunction "A2_A2") (pintype "bidirectional"))
      (node (ref "JP3") (pin "7") (pinfunction "7_7") (pintype "passive"))
    )
    (net (code "92") (name "Net-(B1-PadA3)") (class "Default")
      (node (ref "B1") (pin "A3") (pinfunction "A3_A3") (pintype "bidirectional"))
      (node (ref "JP3") (pin "6") (pinfunction "6_6") (pintype "passive"))
    )
    (net (code "93") (name "Net-(B1-PadA4)") (class "Default")
      (node (ref "B1") (pin "A4") (pinfunction "A4_A4") (pintype "bidirectional"))
      (node (ref "JP3") (pin "5") (pinfunction "5_5") (pintype "passive"))
    )
    (net (code "94") (name "Net-(B1-PadA5)") (class "Default")
      (node (ref "B1") (pin "A5") (pinfunction "A5_A5") (pintype "bidirectional"))
      (node (ref "JP3") (pin "4") (pinfunction "4_4") (pintype "passive"))
    )
    (net (code "95") (name "Net-(B1-PadA6)") (class "Default")
      (node (ref "B1") (pin "A6") (pinfunction "A6_A6") (pintype "bidirectional"))
      (node (ref "JP3") (pin "3") (pinfunction "3_3") (pintype "passive"))
    )
    (net (code "96") (name "Net-(B1-PadA7)") (class "Default")
      (node (ref "B1") (pin "A7") (pinfunction "A7_A7") (pintype "bidirectional"))
      (node (ref "JP3") (pin "2") (pinfunction "2_2") (pintype "passive"))
    )
    (net (code "97") (name "Net-(B1-PadA8)") (class "Default")
      (node (ref "B1") (pin "A8") (pinfunction "A8_A8") (pintype "bidirectional"))
      (node (ref "JP3") (pin "1") (pinfunction "1_1") (pintype "passive"))
    )
    (net (code "98") (name "Net-(D1-PadA)") (class "Default")
      (node (ref "D1") (pin "A") (pinfunction "A_A") (pintype "passive"))
      (node (ref "F6") (pin "2") (pinfunction "2_2") (pintype "passive"))
    )
    (net (code "99") (name "Net-(JP1-Pad1)") (class "Default")
      (node (ref "JP1") (pin "1") (pinfunction "1_1") (pintype "passive"))
      (node (ref "U$1") (pin "D13") (pinfunction "D13_D13") (pintype "bidirectional"))
    )
    (net (code "100") (name "Net-(JP1-Pad2)") (class "Default")
      (node (ref "JP1") (pin "2") (pinfunction "2_2") (pintype "passive"))
      (node (ref "U$1") (pin "D12") (pinfunction "D12_D12") (pintype "bidirectional"))
    )
    (net (code "101") (name "Net-(JP1-Pad3)") (class "Default")
      (node (ref "JP1") (pin "3") (pinfunction "3_3") (pintype "passive"))
      (node (ref "U$1") (pin "D11") (pinfunction "D11_D11") (pintype "bidirectional"))
    )
    (net (code "102") (name "Net-(JP1-Pad4)") (class "Default")
      (node (ref "JP1") (pin "4") (pinfunction "4_4") (pintype "passive"))
      (node (ref "U$1") (pin "D10") (pinfunction "D10_D10") (pintype "bidirectional"))
    )
    (net (code "103") (name "Net-(JP1-Pad5)") (class "Default")
      (node (ref "JP1") (pin "5") (pinfunction "5_5") (pintype "passive"))
      (node (ref "U$1") (pin "D9") (pinfunction "D9_D9") (pintype "bidirectional"))
    )
    (net (code "104") (name "Net-(JP1-Pad6)") (class "Default")
      (node (ref "JP1") (pin "6") (pinfunction "6_6") (pintype "passive"))
      (node (ref "U$1") (pin "D8") (pinfunction "D8_D8") (pintype "bidirectional"))
    )
    (net (code "105") (name "Net-(JP1-Pad7)") (class "Default")
      (node (ref "JP1") (pin "7") (pinfunction "7_7") (pintype "passive"))
      (node (ref "U$1") (pin "D7") (pinfunction "D7_D7") (pintype "bidirectional"))
    )
    (net (code "106") (name "Net-(JP1-Pad8)") (class "Default")
      (node (ref "JP1") (pin "8") (pinfunction "8_8") (pintype "passive"))
      (node (ref "U$1") (pin "D6") (pinfunction "D6_D6") (pintype "bidirectional"))
    )
    (net (code "107") (name "Net-(JP4-Pad1)") (class "Default")
      (node (ref "JP4") (pin "1") (pinfunction "1_1") (pintype "passive"))
      (node (ref "U$1") (pin "A7") (pinfunction "A7_A7") (pintype "bidirectional"))
    )
    (net (code "108") (name "Net-(JP4-Pad2)") (class "Default")
      (node (ref "JP4") (pin "2") (pinfunction "2_2") (pintype "passive"))
      (node (ref "U$1") (pin "A6") (pinfunction "A6_A6") (pintype "bidirectional"))
    )
    (net (code "109") (name "Net-(JP4-Pad3)") (class "Default")
      (node (ref "JP4") (pin "3") (pinfunction "3_3") (pintype "passive"))
      (node (ref "U$1") (pin "A5") (pinfunction "A5_A5") (pintype "bidirectional"))
    )
    (net (code "110") (name "Net-(JP4-Pad4)") (class "Default")
      (node (ref "JP4") (pin "4") (pinfunction "4_4") (pintype "passive"))
      (node (ref "U$1") (pin "A4") (pinfunction "A4_A4") (pintype "bidirectional"))
    )
    (net (code "111") (name "Net-(JP4-Pad5)") (class "Default")
      (node (ref "JP4") (pin "5") (pinfunction "5_5") (pintype "passive"))
      (node (ref "U$1") (pin "A3") (pinfunction "A3_A3") (pintype "bidirectional"))
    )
    (net (code "112") (name "Net-(JP4-Pad6)") (class "Default")
      (node (ref "JP4") (pin "6") (pinfunction "6_6") (pintype "passive"))
      (node (ref "U$1") (pin "A2") (pinfunction "A2_A2") (pintype "bidirectional"))
    )
    (net (code "113") (name "Net-(JP4-Pad7)") (class "Default")
      (node (ref "JP4") (pin "7") (pinfunction "7_7") (pintype "passive"))
      (node (ref "U$1") (pin "A1") (pinfunction "A1_A1") (pintype "bidirectional"))
    )
    (net (code "114") (name "Net-(JP4-Pad8)") (class "Default")
      (node (ref "JP4") (pin "8") (pinfunction "8_8") (pintype "passive"))
      (node (ref "U$1") (pin "A0") (pinfunction "A0_A0") (pintype "bidirectional"))
    )
    (net (code "115") (name "Net-(JP9-Pad1)") (class "Default")
      (node (ref "JP9") (pin "1") (pinfunction "1_1") (pintype "passive"))
      (node (ref "U$1") (pin "RX1") (pinfunction "RX1_RX1") (pintype "bidirectional"))
    )
    (net (code "116") (name "Net-(JP9-Pad2)") (class "Default")
      (node (ref "JP9") (pin "2") (pinfunction "2_2") (pintype "passive"))
      (node (ref "U$1") (pin "TX0") (pinfunction "TX0_TX0") (pintype "bidirectional"))
    )
    (net (code "117") (name "Net-(LED12V-C)") (class "Default")
      (node (ref "LED12V") (pin "K") (pinfunction "C_K") (pintype "passive"))
      (node (ref "R4") (pin "2") (pinfunction "2_2") (pintype "passive"))
    )
    (net (code "118") (name "Net-(LED24V-C)") (class "Default")
      (node (ref "LED24V") (pin "K") (pinfunction "C_K") (pintype "passive"))
      (node (ref "R1") (pin "2") (pinfunction "2_2") (pintype "passive"))
    )
    (net (code "119") (name "PWM.A") (class "Default")
      (node (ref "B1") (pin "13") (pinfunction "13_13") (pintype "bidirectional"))
      (node (ref "DRIVER.1") (pin "2") (pinfunction "2_2") (pintype "passive"))
    )
    (net (code "120") (name "PWM.B") (class "Default")
      (node (ref "B1") (pin "12") (pinfunction "12_12") (pintype "bidirectional"))
      (node (ref "DRIVER.1") (pin "4") (pinfunction "4_4") (pintype "passive"))
    )
    (net (code "121") (name "PWM.C") (class "Default")
      (node (ref "B1") (pin "11") (pinfunction "11_11") (pintype "bidirectional"))
      (node (ref "DRIVER.2") (pin "2") (pinfunction "2_2") (pintype "passive"))
    )
    (net (code "122") (name "PWM.D") (class "Default")
      (node (ref "B1") (pin "10") (pinfunction "10_10") (pintype "bidirectional"))
      (node (ref "DRIVER.2") (pin "4") (pinfunction "4_4") (pintype "passive"))
    )
    (net (code "123") (name "RESET.MEGA") (class "Default")
      (node (ref "B1") (pin "RESET") (pinfunction "~{RESET}_RESET") (pintype "bidirectional"))
      (node (ref "R5") (pin "1") (pinfunction "1_1") (pintype "passive"))
      (node (ref "U$2") (pin "2") (pinfunction "2_2") (pintype "bidirectional"))
    )
    (net (code "124") (name "RX.BLUE") (class "Default")
      (node (ref "BLUETOOTH") (pin "2") (pinfunction "2_2") (pintype "passive"))
      (node (ref "R2") (pin "1") (pinfunction "1_1") (pintype "passive"))
      (node (ref "R3") (pin "2") (pinfunction "2_2") (pintype "passive"))
    )
    (net (code "125") (name "RX.NANO") (class "Default")
      (node (ref "B1") (pin "16") (pinfunction "16(TX2)_16") (pintype "bidirectional"))
      (node (ref "U$1") (pin "D5") (pinfunction "D5_D5") (pintype "bidirectional"))
    )
    (net (code "126") (name "STATE") (class "Default")
      (node (ref "BLUETOOTH") (pin "1") (pinfunction "1_1") (pintype "passive"))
    )
    (net (code "127") (name "TX.BLUE") (class "Default")
      (node (ref "B1") (pin "15") (pinfunction "15(RX3)_15") (pintype "bidirectional"))
      (node (ref "BLUETOOTH") (pin "3") (pinfunction "3_3") (pintype "passive"))
    )
    (net (code "128") (name "TX.MEGA") (class "Default")
      (node (ref "B1") (pin "14") (pinfunction "14(TX3)_14") (pintype "bidirectional"))
      (node (ref "R2") (pin "2") (pinfunction "2_2") (pintype "passive"))
    )
    (net (code "129") (name "TX.NANO") (class "Default")
      (node (ref "B1") (pin "17") (pinfunction "17(RX2)_17") (pintype "bidirectional"))
      (node (ref "U$1") (pin "D4") (pinfunction "D4_D4") (pintype "bidirectional"))
    )
    (net (code "130") (name "unconnected-(B1-Pad3.3V)") (class "Default")
      (node (ref "B1") (pin "3.3V") (pinfunction "3.3V_3.3V") (pintype "bidirectional"))
    )
    (net (code "131") (name "unconnected-(B1-PadAREF)") (class "Default")
      (node (ref "B1") (pin "AREF") (pinfunction "AREF_AREF") (pintype "bidirectional"))
    )
    (net (code "132") (name "unconnected-(B1-PadIOREF)") (class "Default")
      (node (ref "B1") (pin "IOREF") (pinfunction "IOREF_IOREF") (pintype "bidirectional"))
    )
    (net (code "133") (name "unconnected-(B1-PadSCL)") (class "Default")
      (node (ref "B1") (pin "SCL") (pinfunction "SCL_SCL") (pintype "bidirectional"))
    )
    (net (code "134") (name "unconnected-(B1-PadSDA)") (class "Default")
      (node (ref "B1") (pin "SDA") (pinfunction "SDA_SDA") (pintype "bidirectional"))
    )
    (net (code "135") (name "unconnected-(U$1-PadAREF)") (class "Default")
      (node (ref "U$1") (pin "AREF") (pinfunction "AREF_AREF") (pintype "bidirectional"))
    )
    (net (code "136") (name "unconnected-(U$1-PadRST)") (class "Default")
      (node (ref "U$1") (pin "RST") (pinfunction "RST_RST") (pintype "bidirectional"))
    )
    (net (code "137") (name "unconnected-(U$1-PadRST1)") (class "Default")
      (node (ref "U$1") (pin "RST1") (pinfunction "RST1_RST1") (pintype "bidirectional"))
    )
  )
)
